# fb_atmega_2te.net
KiCad netlist of a schematic drawn in EAGLE
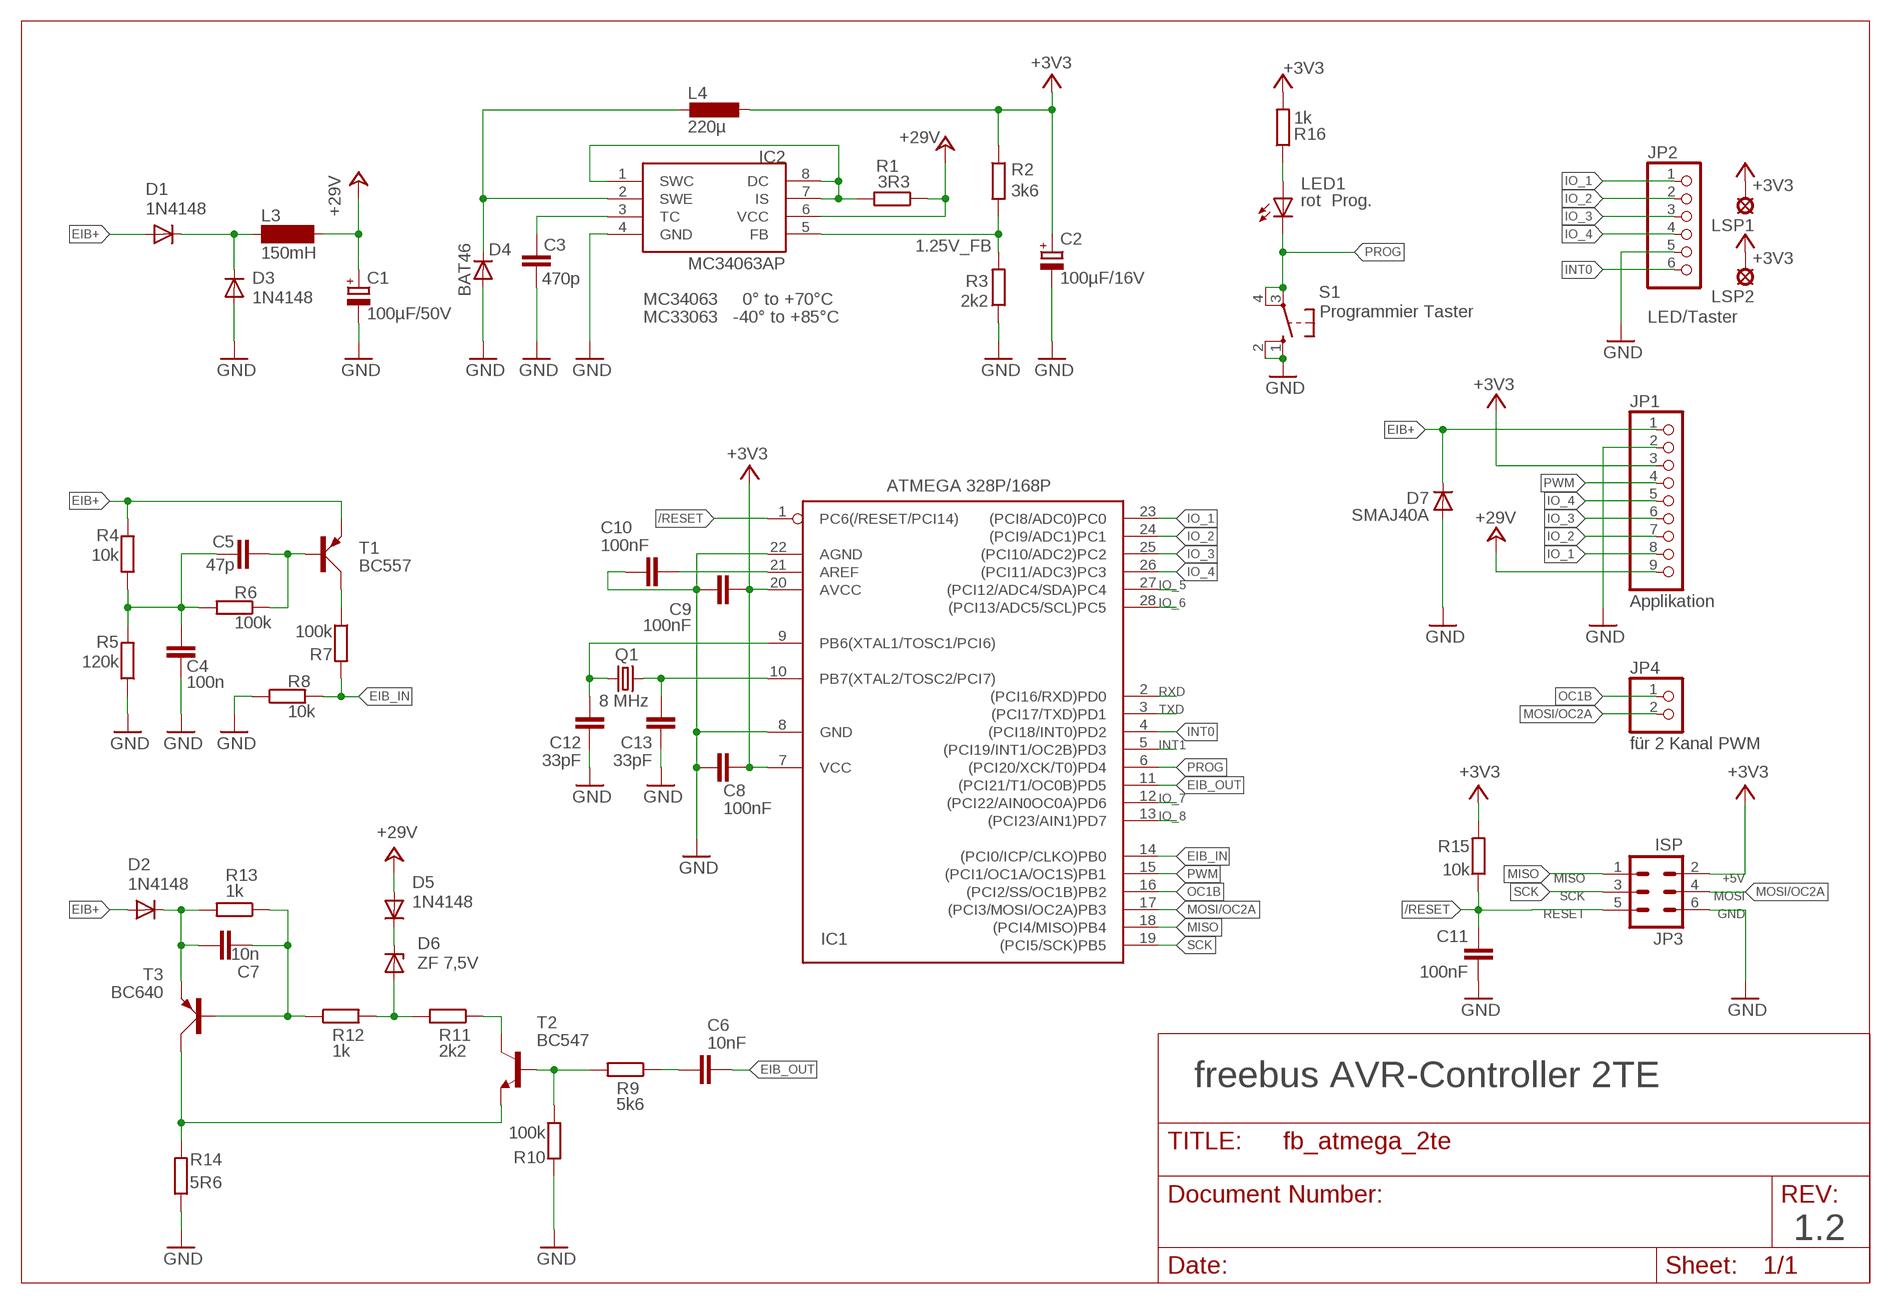
[diagram p0: schematic, sheet 1]

(export (version "E")
  (design (tool "Eeschema 10.0.6"))
  (components
    (comp (ref "C1")
      (value "100µF/50V")
      (footprint "eagle-import:E3,5-8")
      (libsource (lib "eagle-import") (part "CPOL-EUE3.5-8"))
    )
    (comp (ref "C2")
      (value "100µF/16V")
      (footprint "eagle-import:E2-5")
      (libsource (lib "eagle-import") (part "CPOL-EUE2-5"))
    )
    (comp (ref "C3")
      (value "470p")
      (footprint "eagle-import:C025-024X044")
      (libsource (lib "eagle-import") (part "C-EU025-024X044"))
    )
    (comp (ref "C4")
      (value "100n")
      (footprint "eagle-import:C025-024X044")
      (libsource (lib "eagle-import") (part "C-EU025-024X044"))
    )
    (comp (ref "C5")
      (value "47p")
      (footprint "eagle-import:C025-024X044")
      (libsource (lib "eagle-import") (part "C-EU025-024X044"))
    )
    (comp (ref "C6")
      (value "10nF")
      (footprint "eagle-import:C025-024X044")
      (libsource (lib "eagle-import") (part "C-EU025-024X044"))
    )
    (comp (ref "C7")
      (value "10n")
      (footprint "eagle-import:C025-024X044")
      (libsource (lib "eagle-import") (part "C-EU025-024X044"))
    )
    (comp (ref "C8")
      (value "100nF")
      (footprint "eagle-import:C0805")
      (libsource (lib "eagle-import") (part "C-EUC0805"))
    )
    (comp (ref "C9")
      (value "100nF")
      (footprint "eagle-import:C0805")
      (libsource (lib "eagle-import") (part "C-EUC0805"))
    )
    (comp (ref "C10")
      (value "100nF")
      (footprint "eagle-import:C0805")
      (libsource (lib "eagle-import") (part "C-EUC0805"))
    )
    (comp (ref "C11")
      (value "100nF")
      (footprint "eagle-import:C025-024X044")
      (libsource (lib "eagle-import") (part "C-EU025-024X044"))
    )
    (comp (ref "C12")
      (value "33pF")
      (footprint "eagle-import:C0805")
      (libsource (lib "eagle-import") (part "C-EUC0805"))
    )
    (comp (ref "C13")
      (value "33pF")
      (footprint "eagle-import:C0805")
      (libsource (lib "eagle-import") (part "C-EUC0805"))
    )
    (comp (ref "D1")
      (value "1N4148")
      (footprint "eagle-import:D-2.5")
      (libsource (lib "eagle-import") (part "1N4148"))
    )
    (comp (ref "D2")
      (value "1N4148")
      (footprint "eagle-import:D-2.5")
      (libsource (lib "eagle-import") (part "1N4148"))
    )
    (comp (ref "D3")
      (value "1N4148")
      (footprint "eagle-import:D-2.5")
      (libsource (lib "eagle-import") (part "1N4148"))
    )
    (comp (ref "D4")
      (value "BAT46")
      (footprint "eagle-import:D-2.5")
      (libsource (lib "eagle-import") (part "1N4148"))
    )
    (comp (ref "D5")
      (value "1N4148")
      (footprint "eagle-import:D-2.5")
      (libsource (lib "eagle-import") (part "1N4148"))
    )
    (comp (ref "D6")
      (value "ZF 7,5V")
      (footprint "eagle-import:ZDIO-2.5")
      (libsource (lib "eagle-import") (part "ZENER-DIODEZD-2.5"))
    )
    (comp (ref "D7")
      (value "SMAJ40A")
      (footprint "eagle-import:SMB")
      (libsource (lib "eagle-import") (part "D-SMB"))
    )
    (comp (ref "IC1")
      (value "ATMEGA 328P/168P")
      (footprint "eagle-import:DIL28-3")
      (libsource (lib "eagle-import") (part "ATMEGA168P-20"))
    )
    (comp (ref "IC2")
      (value "MC34063AP")
      (footprint "eagle-import:DIL08")
      (libsource (lib "eagle-import") (part "MC34063AP"))
    )
    (comp (ref "JP1")
      (value "Applikation")
      (footprint "eagle-import:1X09")
      (libsource (lib "eagle-import") (part "PINHD-1X9"))
    )
    (comp (ref "JP2")
      (value "LED/Taster")
      (footprint "eagle-import:1X06")
      (libsource (lib "eagle-import") (part "PINHD-1X6"))
    )
    (comp (ref "JP3")
      (value "ISP")
      (footprint "eagle-import:2X03")
      (libsource (lib "eagle-import") (part "ISP_6POLPINHD2X3"))
    )
    (comp (ref "JP4")
      (value "für 2 Kanal PWM")
      (footprint "eagle-import:1X02")
      (libsource (lib "eagle-import") (part "PINHD-1X2"))
    )
    (comp (ref "L3")
      (value "150mH")
      (footprint "eagle-import:BS11")
      (libsource (lib "eagle-import") (part "BS11"))
    )
    (comp (ref "L4")
      (value "220µ")
      (footprint "eagle-import:0207_2V")
      (libsource (lib "eagle-import") (part "L-EU0207/2V"))
    )
    (comp (ref "LED1")
      (value "rot Prog.")
      (footprint "eagle-import:LED3MM")
      (libsource (lib "eagle-import") (part "LED3MM"))
    )
    (comp (ref "LSP1")
      (value "LSP10")
      (footprint "eagle-import:LSP10")
      (libsource (lib "eagle-import") (part "LSP10"))
    )
    (comp (ref "LSP2")
      (value "LSP10")
      (footprint "eagle-import:LSP10")
      (libsource (lib "eagle-import") (part "LSP10"))
    )
    (comp (ref "Q1")
      (value "8 MHz")
      (footprint "eagle-import:HC49U-V")
      (libsource (lib "eagle-import") (part "CRYSTALHC49U-V"))
    )
    (comp (ref "R1")
      (value "3R3")
      (footprint "eagle-import:0207_2V")
      (libsource (lib "eagle-import") (part "R-EU_0207/2V"))
    )
    (comp (ref "R2")
      (value "3k6")
      (footprint "eagle-import:0207_2V")
      (libsource (lib "eagle-import") (part "R-EU_0207/2V"))
    )
    (comp (ref "R3")
      (value "2k2")
      (footprint "eagle-import:0207_2V")
      (libsource (lib "eagle-import") (part "R-EU_0207/2V"))
    )
    (comp (ref "R4")
      (value "10k")
      (footprint "eagle-import:0207_2V")
      (libsource (lib "eagle-import") (part "R-EU_0207/2V"))
    )
    (comp (ref "R5")
      (value "120k")
      (footprint "eagle-import:0207_2V")
      (libsource (lib "eagle-import") (part "R-EU_0207/2V"))
    )
    (comp (ref "R6")
      (value "100k")
      (footprint "eagle-import:0207_2V")
      (libsource (lib "eagle-import") (part "R-EU_0207/2V"))
    )
    (comp (ref "R7")
      (value "100k")
      (footprint "eagle-import:0207_2V")
      (libsource (lib "eagle-import") (part "R-EU_0207/2V"))
    )
    (comp (ref "R8")
      (value "10k")
      (footprint "eagle-import:0207_2V")
      (libsource (lib "eagle-import") (part "R-EU_0207/2V"))
    )
    (comp (ref "R9")
      (value "5k6")
      (footprint "eagle-import:0207_2V")
      (libsource (lib "eagle-import") (part "R-EU_0207/2V"))
    )
    (comp (ref "R10")
      (value "100k")
      (footprint "eagle-import:0207_2V")
      (libsource (lib "eagle-import") (part "R-EU_0207/2V"))
    )
    (comp (ref "R11")
      (value "2k2")
      (footprint "eagle-import:0207_2V")
      (libsource (lib "eagle-import") (part "R-EU_0207/2V"))
    )
    (comp (ref "R12")
      (value "1k")
      (footprint "eagle-import:0207_2V")
      (libsource (lib "eagle-import") (part "R-EU_0207/2V"))
    )
    (comp (ref "R13")
      (value "1k")
      (footprint "eagle-import:0207_2V")
      (libsource (lib "eagle-import") (part "R-EU_0207/2V"))
    )
    (comp (ref "R14")
      (value "5R6")
      (footprint "eagle-import:0207_2V")
      (libsource (lib "eagle-import") (part "R-EU_0207/2V"))
    )
    (comp (ref "R15")
      (value "10k")
      (footprint "eagle-import:0207_2V")
      (libsource (lib "eagle-import") (part "R-EU_0207/2V"))
    )
    (comp (ref "R16")
      (value "1k")
      (footprint "eagle-import:0207_2V")
      (libsource (lib "eagle-import") (part "R-EU_0207/2V"))
    )
    (comp (ref "S1")
      (value "Programmier Taster")
      (footprint "eagle-import:B3F-10XX")
      (fields (field (name "MPN") "B3F-1000"))
      (libsource (lib "eagle-import") (part "10-XX"))
    )
    (comp (ref "T1")
      (value "BC557")
      (footprint "eagle-import:SOT54A")
      (libsource (lib "eagle-import") (part "BC557"))
    )
    (comp (ref "T2")
      (value "BC547")
      (footprint "eagle-import:TO92")
      (libsource (lib "eagle-import") (part "BC547"))
    )
    (comp (ref "T3")
      (value "BC640")
      (footprint "eagle-import:SOT54D")
      (libsource (lib "eagle-import") (part "BC640"))
    )
  )
  (nets
    (net (code "1") (name "+3V3") (class "Default")
      (node (ref "C2") (pin "+") (pinfunction "+_+") (pintype "passive"))
      (node (ref "C8") (pin "1") (pinfunction "1_1") (pintype "passive"))
      (node (ref "C9") (pin "1") (pinfunction "1_1") (pintype "passive"))
      (node (ref "IC1") (pin "20") (pinfunction "AVCC_20") (pintype "bidirectional"))
      (node (ref "IC1") (pin "7") (pinfunction "VCC_7") (pintype "bidirectional"))
      (node (ref "JP1") (pin "3") (pinfunction "3_3") (pintype "passive"))
      (node (ref "JP3") (pin "2") (pinfunction "2_2") (pintype "passive"))
      (node (ref "L4") (pin "1") (pinfunction "1_1") (pintype "passive"))
      (node (ref "LSP1") (pin "MP") (pinfunction "MP_MP") (pintype "passive"))
      (node (ref "LSP2") (pin "MP") (pinfunction "MP_MP") (pintype "passive"))
      (node (ref "R15") (pin "2") (pinfunction "2_2") (pintype "passive"))
      (node (ref "R16") (pin "2") (pinfunction "2_2") (pintype "passive"))
      (node (ref "R2") (pin "1") (pinfunction "1_1") (pintype "passive"))
    )
    (net (code "2") (name "+29V") (class "Default")
      (node (ref "C1") (pin "+") (pinfunction "+_+") (pintype "passive"))
      (node (ref "D5") (pin "A") (pinfunction "A_A") (pintype "passive"))
      (node (ref "IC2") (pin "6") (pinfunction "VCC_6") (pintype "passive"))
      (node (ref "JP1") (pin "9") (pinfunction "9_9") (pintype "passive"))
      (node (ref "L3") (pin "2") (pinfunction "2_2") (pintype "passive"))
      (node (ref "R1") (pin "1") (pinfunction "1_1") (pintype "passive"))
    )
    (net (code "3") (name "/1.25V_FB") (class "Default")
      (node (ref "IC2") (pin "5") (pinfunction "FB_5") (pintype "passive"))
      (node (ref "R2") (pin "2") (pinfunction "2_2") (pintype "passive"))
      (node (ref "R3") (pin "2") (pinfunction "2_2") (pintype "passive"))
    )
    (net (code "4") (name "/INT1") (class "Default")
      (node (ref "IC1") (pin "5") (pinfunction "(PCI19/INT1/OC2B)PD3_5") (pintype "bidirectional"))
    )
    (net (code "5") (name "/IO_5") (class "Default")
      (node (ref "IC1") (pin "27") (pinfunction "(PCI12/ADC4/SDA)PC4_27") (pintype "bidirectional"))
    )
    (net (code "6") (name "/IO_6") (class "Default")
      (node (ref "IC1") (pin "28") (pinfunction "(PCI13/ADC5/SCL)PC5_28") (pintype "bidirectional"))
    )
    (net (code "7") (name "/IO_7") (class "Default")
      (node (ref "IC1") (pin "12") (pinfunction "(PCI22/AIN0OC0A)PD6_12") (pintype "bidirectional"))
    )
    (net (code "8") (name "/IO_8") (class "Default")
      (node (ref "IC1") (pin "13") (pinfunction "(PCI23/AIN1)PD7_13") (pintype "bidirectional"))
    )
    (net (code "9") (name "/RXD") (class "Default")
      (node (ref "IC1") (pin "2") (pinfunction "(PCI16/RXD)PD0_2") (pintype "bidirectional"))
    )
    (net (code "10") (name "/TXD") (class "Default")
      (node (ref "IC1") (pin "3") (pinfunction "(PCI17/TXD)PD1_3") (pintype "bidirectional"))
    )
    (net (code "11") (name "EIB+") (class "Default")
      (node (ref "D1") (pin "A") (pinfunction "A_A") (pintype "passive"))
      (node (ref "D2") (pin "A") (pinfunction "A_A") (pintype "passive"))
      (node (ref "D7") (pin "1") (pinfunction "C_1") (pintype "passive"))
      (node (ref "JP1") (pin "1") (pinfunction "1_1") (pintype "passive"))
      (node (ref "R4") (pin "2") (pinfunction "2_2") (pintype "passive"))
      (node (ref "T1") (pin "E") (pinfunction "E_E") (pintype "passive"))
    )
    (net (code "12") (name "EIB_IN") (class "Default")
      (node (ref "IC1") (pin "14") (pinfunction "(PCI0/ICP/CLKO)PB0_14") (pintype "bidirectional"))
      (node (ref "R7") (pin "2") (pinfunction "2_2") (pintype "passive"))
      (node (ref "R8") (pin "2") (pinfunction "2_2") (pintype "passive"))
    )
    (net (code "13") (name "EIB_OUT") (class "Default")
      (node (ref "C6") (pin "2") (pinfunction "2_2") (pintype "passive"))
      (node (ref "IC1") (pin "11") (pinfunction "(PCI21/T1/OC0B)PD5_11") (pintype "bidirectional"))
    )
    (net (code "14") (name "GND") (class "Default")
      (node (ref "C1") (pin "-") (pinfunction "-_-") (pintype "passive"))
      (node (ref "C10") (pin "1") (pinfunction "1_1") (pintype "passive"))
      (node (ref "C11") (pin "1") (pinfunction "1_1") (pintype "passive"))
      (node (ref "C12") (pin "2") (pinfunction "2_2") (pintype "passive"))
      (node (ref "C13") (pin "2") (pinfunction "2_2") (pintype "passive"))
      (node (ref "C2") (pin "-") (pinfunction "-_-") (pintype "passive"))
      (node (ref "C3") (pin "1") (pinfunction "1_1") (pintype "passive"))
      (node (ref "C4") (pin "1") (pinfunction "1_1") (pintype "passive"))
      (node (ref "C8") (pin "2") (pinfunction "2_2") (pintype "passive"))
      (node (ref "C9") (pin "2") (pinfunction "2_2") (pintype "passive"))
      (node (ref "D3") (pin "A") (pinfunction "A_A") (pintype "passive"))
      (node (ref "D4") (pin "A") (pinfunction "A_A") (pintype "passive"))
      (node (ref "D7") (pin "2") (pinfunction "A_2") (pintype "passive"))
      (node (ref "IC1") (pin "22") (pinfunction "AGND_22") (pintype "bidirectional"))
      (node (ref "IC1") (pin "8") (pinfunction "GND_8") (pintype "bidirectional"))
      (node (ref "IC2") (pin "4") (pinfunction "GND_4") (pintype "passive"))
      (node (ref "JP1") (pin "2") (pinfunction "2_2") (pintype "passive"))
      (node (ref "JP2") (pin "5") (pinfunction "5_5") (pintype "passive"))
      (node (ref "JP3") (pin "6") (pinfunction "6_6") (pintype "passive"))
      (node (ref "R10") (pin "2") (pinfunction "2_2") (pintype "passive"))
      (node (ref "R14") (pin "1") (pinfunction "1_1") (pintype "passive"))
      (node (ref "R3") (pin "1") (pinfunction "1_1") (pintype "passive"))
      (node (ref "R5") (pin "1") (pinfunction "1_1") (pintype "passive"))
      (node (ref "R8") (pin "1") (pinfunction "1_1") (pintype "passive"))
      (node (ref "S1") (pin "1") (pinfunction "S_1") (pintype "passive"))
      (node (ref "S1") (pin "2") (pinfunction "S1_2") (pintype "passive"))
    )
    (net (code "15") (name "INT0") (class "Default")
      (node (ref "IC1") (pin "4") (pinfunction "(PCI18/INT0)PD2_4") (pintype "bidirectional"))
      (node (ref "JP2") (pin "6") (pinfunction "6_6") (pintype "passive"))
    )
    (net (code "16") (name "IO_1") (class "Default")
      (node (ref "IC1") (pin "23") (pinfunction "(PCI8/ADC0)PC0_23") (pintype "bidirectional"))
      (node (ref "JP1") (pin "8") (pinfunction "8_8") (pintype "passive"))
      (node (ref "JP2") (pin "1") (pinfunction "1_1") (pintype "passive"))
    )
    (net (code "17") (name "IO_2") (class "Default")
      (node (ref "IC1") (pin "24") (pinfunction "(PCI9/ADC1)PC1_24") (pintype "bidirectional"))
      (node (ref "JP1") (pin "7") (pinfunction "7_7") (pintype "passive"))
      (node (ref "JP2") (pin "2") (pinfunction "2_2") (pintype "passive"))
    )
    (net (code "18") (name "IO_3") (class "Default")
      (node (ref "IC1") (pin "25") (pinfunction "(PCI10/ADC2)PC2_25") (pintype "bidirectional"))
      (node (ref "JP1") (pin "6") (pinfunction "6_6") (pintype "passive"))
      (node (ref "JP2") (pin "3") (pinfunction "3_3") (pintype "passive"))
    )
    (net (code "19") (name "IO_4") (class "Default")
      (node (ref "IC1") (pin "26") (pinfunction "(PCI11/ADC3)PC3_26") (pintype "bidirectional"))
      (node (ref "JP1") (pin "5") (pinfunction "5_5") (pintype "passive"))
      (node (ref "JP2") (pin "4") (pinfunction "4_4") (pintype "passive"))
    )
    (net (code "20") (name "MISO") (class "Default")
      (node (ref "IC1") (pin "18") (pinfunction "(PCI4/MISO)PB4_18") (pintype "bidirectional"))
      (node (ref "JP3") (pin "1") (pinfunction "1_1") (pintype "passive"))
    )
    (net (code "21") (name "MOSI{slash}OC2A") (class "Default")
      (node (ref "IC1") (pin "17") (pinfunction "(PCI3/MOSI/OC2A)PB3_17") (pintype "bidirectional"))
      (node (ref "JP3") (pin "4") (pinfunction "4_4") (pintype "passive"))
      (node (ref "JP4") (pin "2") (pinfunction "2_2") (pintype "passive"))
    )
    (net (code "22") (name "Net-(C4-Pad2)") (class "Default")
      (node (ref "C4") (pin "2") (pinfunction "2_2") (pintype "passive"))
      (node (ref "C5") (pin "1") (pinfunction "1_1") (pintype "passive"))
      (node (ref "R4") (pin "1") (pinfunction "1_1") (pintype "passive"))
      (node (ref "R5") (pin "2") (pinfunction "2_2") (pintype "passive"))
      (node (ref "R6") (pin "2") (pinfunction "2_2") (pintype "passive"))
    )
    (net (code "23") (name "Net-(C5-Pad2)") (class "Default")
      (node (ref "C5") (pin "2") (pinfunction "2_2") (pintype "passive"))
      (node (ref "R6") (pin "1") (pinfunction "1_1") (pintype "passive"))
      (node (ref "T1") (pin "B") (pinfunction "B_B") (pintype "passive"))
    )
    (net (code "24") (name "Net-(C6-Pad1)") (class "Default")
      (node (ref "C6") (pin "1") (pinfunction "1_1") (pintype "passive"))
      (node (ref "R9") (pin "1") (pinfunction "1_1") (pintype "passive"))
    )
    (net (code "25") (name "Net-(C7-Pad1)") (class "Default")
      (node (ref "C7") (pin "1") (pinfunction "1_1") (pintype "passive"))
      (node (ref "D2") (pin "C") (pinfunction "C_C") (pintype "passive"))
      (node (ref "R13") (pin "2") (pinfunction "2_2") (pintype "passive"))
      (node (ref "T3") (pin "E") (pinfunction "E_E") (pintype "passive"))
    )
    (net (code "26") (name "Net-(C7-Pad2)") (class "Default")
      (node (ref "C7") (pin "2") (pinfunction "2_2") (pintype "passive"))
      (node (ref "R12") (pin "1") (pinfunction "1_1") (pintype "passive"))
      (node (ref "R13") (pin "1") (pinfunction "1_1") (pintype "passive"))
      (node (ref "T3") (pin "B") (pinfunction "B_B") (pintype "passive"))
    )
    (net (code "27") (name "Net-(D1-PadC)") (class "Default")
      (node (ref "D1") (pin "C") (pinfunction "C_C") (pintype "passive"))
      (node (ref "D3") (pin "C") (pinfunction "C_C") (pintype "passive"))
      (node (ref "L3") (pin "1") (pinfunction "1_1") (pintype "passive"))
    )
    (net (code "28") (name "Net-(D5-PadC)") (class "Default")
      (node (ref "D5") (pin "C") (pinfunction "C_C") (pintype "passive"))
      (node (ref "D6") (pin "C") (pinfunction "C_C") (pintype "passive"))
    )
    (net (code "29") (name "Net-(D6-PadA)") (class "Default")
      (node (ref "D6") (pin "A") (pinfunction "A_A") (pintype "passive"))
      (node (ref "R11") (pin "2") (pinfunction "2_2") (pintype "passive"))
      (node (ref "R12") (pin "2") (pinfunction "2_2") (pintype "passive"))
    )
    (net (code "30") (name "Net-(IC1-AREF)") (class "Default")
      (node (ref "C10") (pin "2") (pinfunction "2_2") (pintype "passive"))
      (node (ref "IC1") (pin "21") (pinfunction "AREF_21") (pintype "bidirectional"))
    )
    (net (code "31") (name "Net-(IC1-PB6(XTAL1{slash}TOSC1{slash}PCI6))") (class "Default")
      (node (ref "C12") (pin "1") (pinfunction "1_1") (pintype "passive"))
      (node (ref "IC1") (pin "9") (pinfunction "PB6(XTAL1/TOSC1/PCI6)_9") (pintype "bidirectional"))
      (node (ref "Q1") (pin "1") (pinfunction "1_1") (pintype "passive"))
    )
    (net (code "32") (name "Net-(IC1-PB7(XTAL2{slash}TOSC2{slash}PCI7))") (class "Default")
      (node (ref "C13") (pin "1") (pinfunction "1_1") (pintype "passive"))
      (node (ref "IC1") (pin "10") (pinfunction "PB7(XTAL2/TOSC2/PCI7)_10") (pintype "bidirectional"))
      (node (ref "Q1") (pin "2") (pinfunction "2_2") (pintype "passive"))
    )
    (net (code "33") (name "Net-(IC2-DC)") (class "Default")
      (node (ref "IC2") (pin "1") (pinfunction "SWC_1") (pintype "passive"))
      (node (ref "IC2") (pin "7") (pinfunction "IS_7") (pintype "passive"))
      (node (ref "IC2") (pin "8") (pinfunction "DC_8") (pintype "passive"))
      (node (ref "R1") (pin "2") (pinfunction "2_2") (pintype "passive"))
    )
    (net (code "34") (name "Net-(IC2-SWE)") (class "Default")
      (node (ref "D4") (pin "C") (pinfunction "C_C") (pintype "passive"))
      (node (ref "IC2") (pin "2") (pinfunction "SWE_2") (pintype "passive"))
      (node (ref "L4") (pin "2") (pinfunction "2_2") (pintype "passive"))
    )
    (net (code "35") (name "Net-(IC2-TC)") (class "Default")
      (node (ref "C3") (pin "2") (pinfunction "2_2") (pintype "passive"))
      (node (ref "IC2") (pin "3") (pinfunction "TC_3") (pintype "passive"))
    )
    (net (code "36") (name "Net-(LED1-PadA)") (class "Default")
      (node (ref "LED1") (pin "A") (pinfunction "A_A") (pintype "passive"))
      (node (ref "R16") (pin "1") (pinfunction "1_1") (pintype "passive"))
    )
    (net (code "37") (name "Net-(R7-Pad1)") (class "Default")
      (node (ref "R7") (pin "1") (pinfunction "1_1") (pintype "passive"))
      (node (ref "T1") (pin "C") (pinfunction "C_C") (pintype "passive"))
    )
    (net (code "38") (name "Net-(T2-B)") (class "Default")
      (node (ref "R10") (pin "1") (pinfunction "1_1") (pintype "passive"))
      (node (ref "R9") (pin "2") (pinfunction "2_2") (pintype "passive"))
      (node (ref "T2") (pin "2") (pinfunction "B_2") (pintype "passive"))
    )
    (net (code "39") (name "Net-(T2-C)") (class "Default")
      (node (ref "R11") (pin "1") (pinfunction "1_1") (pintype "passive"))
      (node (ref "T2") (pin "3") (pinfunction "C_3") (pintype "passive"))
    )
    (net (code "40") (name "Net-(T2-E)") (class "Default")
      (node (ref "R14") (pin "2") (pinfunction "2_2") (pintype "passive"))
      (node (ref "T2") (pin "1") (pinfunction "E_1") (pintype "passive"))
      (node (ref "T3") (pin "C") (pinfunction "C_C") (pintype "passive"))
    )
    (net (code "41") (name "OC1B") (class "Default")
      (node (ref "IC1") (pin "16") (pinfunction "(PCI2/SS/OC1B)PB2_16") (pintype "bidirectional"))
      (node (ref "JP4") (pin "1") (pinfunction "1_1") (pintype "passive"))
    )
    (net (code "42") (name "PROG") (class "Default")
      (node (ref "IC1") (pin "6") (pinfunction "(PCI20/XCK/T0)PD4_6") (pintype "bidirectional"))
      (node (ref "LED1") (pin "K") (pinfunction "C_K") (pintype "passive"))
      (node (ref "S1") (pin "3") (pinfunction "P_3") (pintype "passive"))
      (node (ref "S1") (pin "4") (pinfunction "P1_4") (pintype "passive"))
    )
    (net (code "43") (name "PWM") (class "Default")
      (node (ref "IC1") (pin "15") (pinfunction "(PCI1/OC1A/OC1S)PB1_15") (pintype "bidirectional"))
      (node (ref "JP1") (pin "4") (pinfunction "4_4") (pintype "passive"))
    )
    (net (code "44") (name "SCK") (class "Default")
      (node (ref "IC1") (pin "19") (pinfunction "(PCI5/SCK)PB5_19") (pintype "bidirectional"))
      (node (ref "JP3") (pin "3") (pinfunction "3_3") (pintype "passive"))
    )
    (net (code "45") (name "{slash}RESET") (class "Default")
      (node (ref "C11") (pin "2") (pinfunction "2_2") (pintype "passive"))
      (node (ref "IC1") (pin "1") (pinfunction "PC6(/RESET/PCI14)_1") (pintype "bidirectional"))
      (node (ref "JP3") (pin "5") (pinfunction "5_5") (pintype "passive"))
      (node (ref "R15") (pin "1") (pinfunction "1_1") (pintype "passive"))
    )
  )
)
